# Overall_Circuit.net
KiCad netlist of a schematic drawn in EAGLE
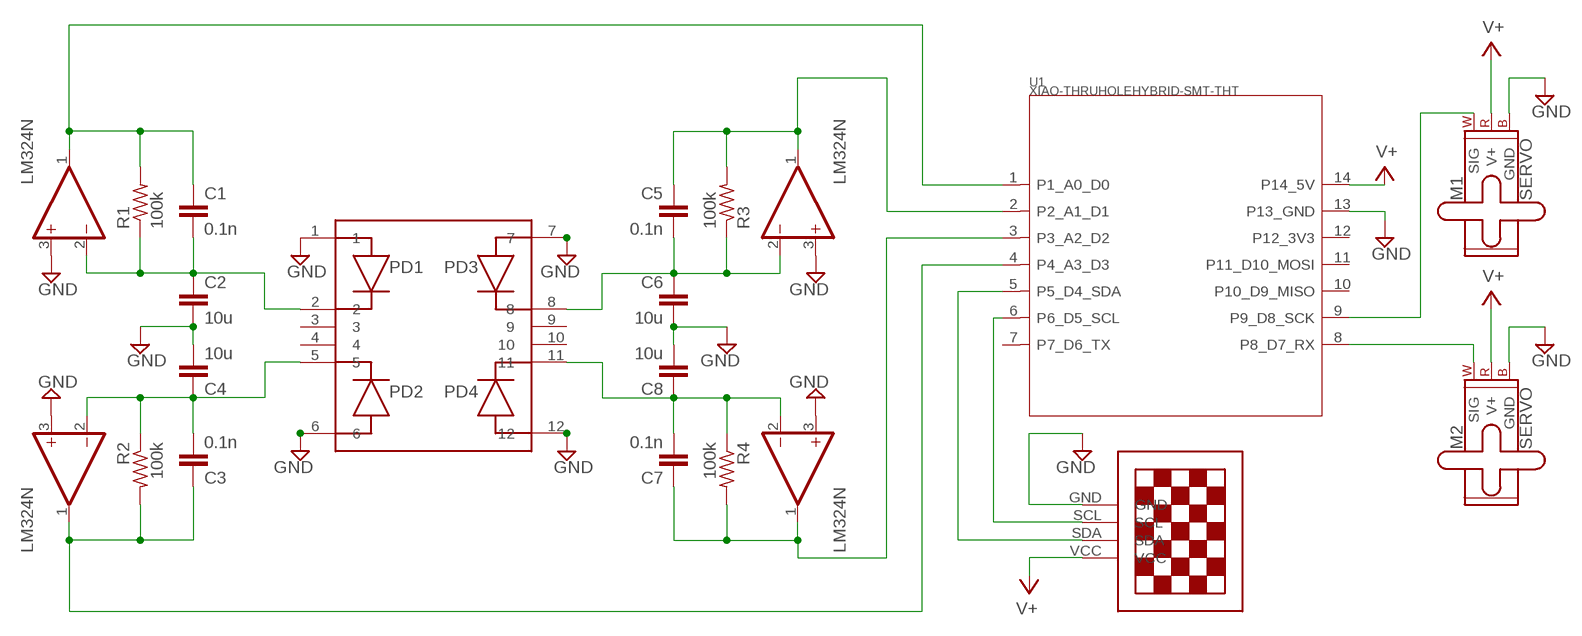
[diagram p0: schematic, sheet 1]

(export (version "E")
  (design (tool "Eeschema 10.0.6"))
  (components
    (comp (ref "C1")
      (value "0.1n")
      (footprint "eagle-import:C0805")
      (libsource (lib "eagle-import") (part "C-EUC0805"))
    )
    (comp (ref "C2")
      (value "10u")
      (footprint "eagle-import:C0805")
      (libsource (lib "eagle-import") (part "C-EUC0805"))
    )
    (comp (ref "C3")
      (value "0.1n")
      (footprint "eagle-import:C0805")
      (libsource (lib "eagle-import") (part "C-EUC0805"))
    )
    (comp (ref "C4")
      (value "10u")
      (footprint "eagle-import:C0805")
      (libsource (lib "eagle-import") (part "C-EUC0805"))
    )
    (comp (ref "C5")
      (value "0.1n")
      (footprint "eagle-import:C0805")
      (libsource (lib "eagle-import") (part "C-EUC0805"))
    )
    (comp (ref "C6")
      (value "10u")
      (footprint "eagle-import:C0805")
      (libsource (lib "eagle-import") (part "C-EUC0805"))
    )
    (comp (ref "C7")
      (value "0.1n")
      (footprint "eagle-import:C0805")
      (libsource (lib "eagle-import") (part "C-EUC0805"))
    )
    (comp (ref "C8")
      (value "10u")
      (footprint "eagle-import:C0805")
      (libsource (lib "eagle-import") (part "C-EUC0805"))
    )
    (comp (ref "IC1")
      (value "LM324N")
      (footprint "eagle-import:DIL14")
      (libsource (lib "eagle-import") (part "LM324N"))
    )
    (comp (ref "IC2")
      (value "LM324N")
      (footprint "eagle-import:DIL14")
      (libsource (lib "eagle-import") (part "LM324N"))
    )
    (comp (ref "IC3")
      (value "LM324N")
      (footprint "eagle-import:DIL14")
      (libsource (lib "eagle-import") (part "LM324N"))
    )
    (comp (ref "IC4")
      (value "LM324N")
      (footprint "eagle-import:DIL14")
      (libsource (lib "eagle-import") (part "LM324N"))
    )
    (comp (ref "M1")
      (value "SERVO")
      (footprint "eagle-import:1X03")
      (libsource (lib "eagle-import") (part "SERVO"))
    )
    (comp (ref "M2")
      (value "SERVO")
      (footprint "eagle-import:1X03")
      (libsource (lib "eagle-import") (part "SERVO"))
    )
    (comp (ref "R1")
      (value "100k")
      (footprint "eagle-import:R0805")
      (libsource (lib "eagle-import") (part "R-US_R0805"))
    )
    (comp (ref "R2")
      (value "100k")
      (footprint "eagle-import:R0805")
      (libsource (lib "eagle-import") (part "R-US_R0805"))
    )
    (comp (ref "R3")
      (value "100k")
      (footprint "eagle-import:R0805")
      (libsource (lib "eagle-import") (part "R-US_R0805"))
    )
    (comp (ref "R4")
      (value "100k")
      (footprint "eagle-import:R0805")
      (libsource (lib "eagle-import") (part "R-US_R0805"))
    )
    (comp (ref "U$1")
      (value "OPR5925")
      (footprint "eagle-import:OPR5925")
      (libsource (lib "eagle-import") (part "OPR5925"))
    )
    (comp (ref "U$2")
      (value "13\"OLED13\"OLED")
      (footprint "eagle-import:1.3_OLED")
      (libsource (lib "eagle-import") (part "13{dblquote}OLED13{dblquote}OLED"))
    )
    (comp (ref "U1")
      (value "XIAO-THRUHOLEHYBRID-SMT-THT")
      (footprint "eagle-import:XIAO-GENERIC-HYBRID-MODULE14P-2.54-21X17.8MM")
      (libsource (lib "eagle-import") (part "XIAO-THRUHOLEHYBRID-SMT-THT"))
    )
  )
  (nets
    (net (code "1") (name "GND") (class "Default")
      (node (ref "C2") (pin "2") (pinfunction "2_2") (pintype "passive"))
      (node (ref "C4") (pin "2") (pinfunction "2_2") (pintype "passive"))
      (node (ref "C6") (pin "2") (pinfunction "2_2") (pintype "passive"))
      (node (ref "C8") (pin "2") (pinfunction "2_2") (pintype "passive"))
      (node (ref "IC1") (pin "3") (pinfunction "+IN_3") (pintype "input"))
      (node (ref "IC2") (pin "3") (pinfunction "+IN_3") (pintype "input"))
      (node (ref "IC3") (pin "3") (pinfunction "+IN_3") (pintype "input"))
      (node (ref "IC4") (pin "3") (pinfunction "+IN_3") (pintype "input"))
      (node (ref "M1") (pin "3") (pinfunction "GND_3") (pintype "bidirectional"))
      (node (ref "M2") (pin "3") (pinfunction "GND_3") (pintype "bidirectional"))
      (node (ref "U$1") (pin "1") (pinfunction "1_1") (pintype "bidirectional"))
      (node (ref "U$1") (pin "12") (pinfunction "12_12") (pintype "bidirectional"))
      (node (ref "U$1") (pin "6") (pinfunction "6_6") (pintype "bidirectional"))
      (node (ref "U$1") (pin "7") (pinfunction "7_7") (pintype "bidirectional"))
      (node (ref "U$2") (pin "GND") (pinfunction "GND_GND") (pintype "bidirectional"))
      (node (ref "U1") (pin "13") (pinfunction "P13_GND_13") (pintype "bidirectional"))
    )
    (net (code "2") (name "Net-(IC1A--IN)") (class "Default")
      (node (ref "C1") (pin "2") (pinfunction "2_2") (pintype "passive"))
      (node (ref "C2") (pin "1") (pinfunction "1_1") (pintype "passive"))
      (node (ref "IC1") (pin "2") (pinfunction "-IN_2") (pintype "input"))
      (node (ref "R1") (pin "1") (pinfunction "1_1") (pintype "passive"))
      (node (ref "U$1") (pin "2") (pinfunction "2_2") (pintype "bidirectional"))
    )
    (net (code "3") (name "Net-(IC1A-OUT)") (class "Default")
      (node (ref "C1") (pin "1") (pinfunction "1_1") (pintype "passive"))
      (node (ref "IC1") (pin "1") (pinfunction "OUT_1") (pintype "output"))
      (node (ref "R1") (pin "2") (pinfunction "2_2") (pintype "passive"))
      (node (ref "U1") (pin "1") (pinfunction "P1_A0_D0_1") (pintype "bidirectional"))
    )
    (net (code "4") (name "Net-(IC2A--IN)") (class "Default")
      (node (ref "C3") (pin "2") (pinfunction "2_2") (pintype "passive"))
      (node (ref "C4") (pin "1") (pinfunction "1_1") (pintype "passive"))
      (node (ref "IC2") (pin "2") (pinfunction "-IN_2") (pintype "input"))
      (node (ref "R2") (pin "1") (pinfunction "1_1") (pintype "passive"))
      (node (ref "U$1") (pin "5") (pinfunction "5_5") (pintype "bidirectional"))
    )
    (net (code "5") (name "Net-(IC2A-OUT)") (class "Default")
      (node (ref "C3") (pin "1") (pinfunction "1_1") (pintype "passive"))
      (node (ref "IC2") (pin "1") (pinfunction "OUT_1") (pintype "output"))
      (node (ref "R2") (pin "2") (pinfunction "2_2") (pintype "passive"))
      (node (ref "U1") (pin "4") (pinfunction "P4_A3_D3_4") (pintype "bidirectional"))
    )
    (net (code "6") (name "Net-(IC3A--IN)") (class "Default")
      (node (ref "C5") (pin "2") (pinfunction "2_2") (pintype "passive"))
      (node (ref "C6") (pin "1") (pinfunction "1_1") (pintype "passive"))
      (node (ref "IC3") (pin "2") (pinfunction "-IN_2") (pintype "input"))
      (node (ref "R3") (pin "1") (pinfunction "1_1") (pintype "passive"))
      (node (ref "U$1") (pin "8") (pinfunction "8_8") (pintype "bidirectional"))
    )
    (net (code "7") (name "Net-(IC3A-OUT)") (class "Default")
      (node (ref "C5") (pin "1") (pinfunction "1_1") (pintype "passive"))
      (node (ref "IC3") (pin "1") (pinfunction "OUT_1") (pintype "output"))
      (node (ref "R3") (pin "2") (pinfunction "2_2") (pintype "passive"))
      (node (ref "U1") (pin "2") (pinfunction "P2_A1_D1_2") (pintype "bidirectional"))
    )
    (net (code "8") (name "Net-(IC4A--IN)") (class "Default")
      (node (ref "C7") (pin "2") (pinfunction "2_2") (pintype "passive"))
      (node (ref "C8") (pin "1") (pinfunction "1_1") (pintype "passive"))
      (node (ref "IC4") (pin "2") (pinfunction "-IN_2") (pintype "input"))
      (node (ref "R4") (pin "1") (pinfunction "1_1") (pintype "passive"))
      (node (ref "U$1") (pin "11") (pinfunction "11_11") (pintype "bidirectional"))
    )
    (net (code "9") (name "Net-(IC4A-OUT)") (class "Default")
      (node (ref "C7") (pin "1") (pinfunction "1_1") (pintype "passive"))
      (node (ref "IC4") (pin "1") (pinfunction "OUT_1") (pintype "output"))
      (node (ref "R4") (pin "2") (pinfunction "2_2") (pintype "passive"))
      (node (ref "U1") (pin "3") (pinfunction "P3_A2_D2_3") (pintype "bidirectional"))
    )
    (net (code "10") (name "Net-(M1-SIG)") (class "Default")
      (node (ref "M1") (pin "1") (pinfunction "SIG_1") (pintype "bidirectional"))
      (node (ref "U1") (pin "9") (pinfunction "P9_D8_SCK_9") (pintype "bidirectional"))
    )
    (net (code "11") (name "Net-(M2-SIG)") (class "Default")
      (node (ref "M2") (pin "1") (pinfunction "SIG_1") (pintype "bidirectional"))
      (node (ref "U1") (pin "8") (pinfunction "P8_D7_RX_8") (pintype "bidirectional"))
    )
    (net (code "12") (name "Net-(U1-P5_D4_SDA)") (class "Default")
      (node (ref "U$2") (pin "SDA") (pinfunction "SDA_SDA") (pintype "bidirectional"))
      (node (ref "U1") (pin "5") (pinfunction "P5_D4_SDA_5") (pintype "bidirectional"))
    )
    (net (code "13") (name "Net-(U1-P6_D5_SCL)") (class "Default")
      (node (ref "U$2") (pin "SCL") (pinfunction "SCL_SCL") (pintype "bidirectional"))
      (node (ref "U1") (pin "6") (pinfunction "P6_D5_SCL_6") (pintype "bidirectional"))
    )
    (net (code "14") (name "V+") (class "Default")
      (node (ref "M1") (pin "2") (pinfunction "V+_2") (pintype "bidirectional"))
      (node (ref "M2") (pin "2") (pinfunction "V+_2") (pintype "bidirectional"))
      (node (ref "U$2") (pin "VCC") (pinfunction "VCC_VCC") (pintype "bidirectional"))
      (node (ref "U1") (pin "14") (pinfunction "P14_5V_14") (pintype "bidirectional"))
    )
    (net (code "15") (name "unconnected-(U$1-Pad3)") (class "Default")
      (node (ref "U$1") (pin "3") (pinfunction "3_3") (pintype "bidirectional"))
    )
    (net (code "16") (name "unconnected-(U$1-Pad4)") (class "Default")
      (node (ref "U$1") (pin "4") (pinfunction "4_4") (pintype "bidirectional"))
    )
    (net (code "17") (name "unconnected-(U$1-Pad9)") (class "Default")
      (node (ref "U$1") (pin "9") (pinfunction "9_9") (pintype "bidirectional"))
    )
    (net (code "18") (name "unconnected-(U$1-Pad10)") (class "Default")
      (node (ref "U$1") (pin "10") (pinfunction "10_10") (pintype "bidirectional"))
    )
    (net (code "19") (name "unconnected-(U1-P7_D6_TX-Pad7)") (class "Default")
      (node (ref "U1") (pin "7") (pinfunction "P7_D6_TX_7") (pintype "bidirectional"))
    )
    (net (code "20") (name "unconnected-(U1-P10_D9_MISO-Pad10)") (class "Default")
      (node (ref "U1") (pin "10") (pinfunction "P10_D9_MISO_10") (pintype "bidirectional"))
    )
    (net (code "21") (name "unconnected-(U1-P11_D10_MOSI-Pad11)") (class "Default")
      (node (ref "U1") (pin "11") (pinfunction "P11_D10_MOSI_11") (pintype "bidirectional"))
    )
    (net (code "22") (name "unconnected-(U1-P12_3V3-Pad12)") (class "Default")
      (node (ref "U1") (pin "12") (pinfunction "P12_3V3_12") (pintype "bidirectional"))
    )
  )
)
